# 14_SD.net
KiCad netlist of a schematic drawn in Altium Designer
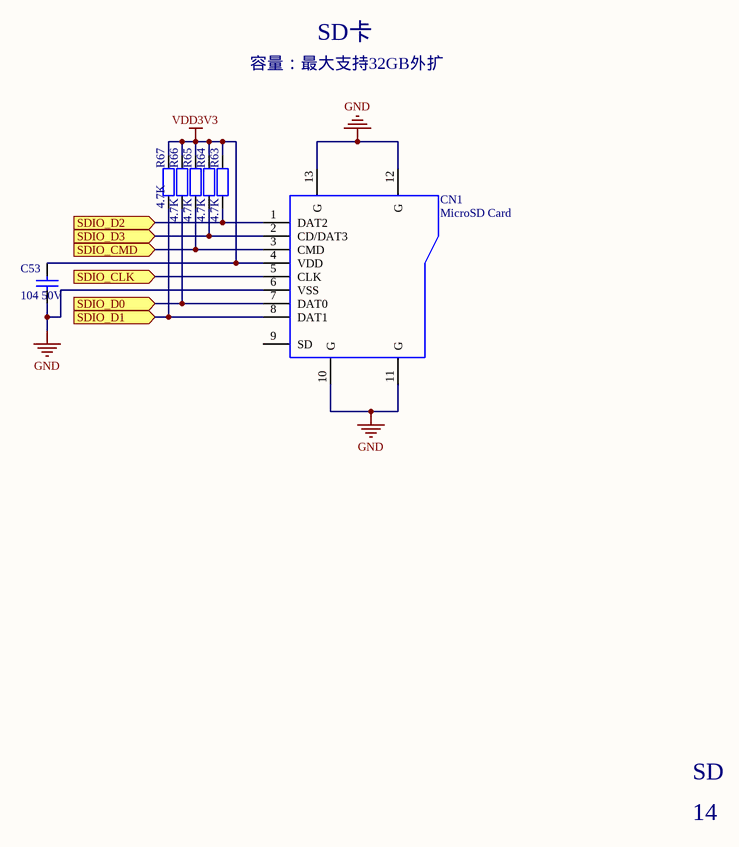
[diagram p0: 14_SD.SchDoc]

(export (version "E")
  (design (tool "Eeschema 10.0.6"))
  (components
    (comp (ref "C53")
      (value "104 50V")
      (footprint "SMD-0603C")
      (description "贴片电容 20%")
      (libsource (lib "XiaoyI") (part "CAP4"))
    )
    (comp (ref "CN1")
      (value "MicroSD Card")
      (footprint "SD_Card_TF")
      (libsource (lib "YS-F1Pro开发板主板") (part "SD Card"))
    )
    (comp (ref "R63")
      (value "4.7K")
      (footprint "SMD-0603")
      (description "贴片电阻 5%")
      (libsource (lib "XiaoyI") (part "RES2"))
    )
    (comp (ref "R64")
      (value "4.7K")
      (footprint "SMD-0603")
      (description "贴片电阻 5%")
      (libsource (lib "XiaoyI") (part "RES2"))
    )
    (comp (ref "R65")
      (value "4.7K")
      (footprint "SMD-0603")
      (description "贴片电阻 5%")
      (libsource (lib "XiaoyI") (part "RES2"))
    )
    (comp (ref "R66")
      (value "4.7K")
      (footprint "SMD-0603")
      (description "贴片电阻 5%")
      (libsource (lib "XiaoyI") (part "RES2"))
    )
    (comp (ref "R67")
      (value "4.7K")
      (footprint "SMD-0603")
      (description "贴片电阻 5%")
      (libsource (lib "XiaoyI") (part "RES2"))
    )
  )
  (nets
    (net (code "1") (name "/SDIO_CLK") (class "Default")
      (node (ref "CN1") (pin "5") (pinfunction "CLK_5") (pintype "passive"))
    )
    (net (code "2") (name "/SDIO_CMD") (class "Default")
      (node (ref "CN1") (pin "3") (pinfunction "CMD_3") (pintype "passive"))
      (node (ref "R65") (pin "2") (pinfunction "2_2") (pintype "passive"))
    )
    (net (code "3") (name "/SDIO_D0") (class "Default")
      (node (ref "CN1") (pin "7") (pinfunction "DAT0_7") (pintype "passive"))
      (node (ref "R66") (pin "2") (pinfunction "2_2") (pintype "passive"))
    )
    (net (code "4") (name "/SDIO_D1") (class "Default")
      (node (ref "CN1") (pin "8") (pinfunction "DAT1_8") (pintype "passive"))
      (node (ref "R67") (pin "2") (pinfunction "2_2") (pintype "passive"))
    )
    (net (code "5") (name "/SDIO_D2") (class "Default")
      (node (ref "CN1") (pin "1") (pinfunction "DAT2_1") (pintype "passive"))
      (node (ref "R63") (pin "2") (pinfunction "2_2") (pintype "passive"))
    )
    (net (code "6") (name "/SDIO_D3") (class "Default")
      (node (ref "CN1") (pin "2") (pinfunction "CD/DAT3_2") (pintype "passive"))
      (node (ref "R64") (pin "2") (pinfunction "2_2") (pintype "passive"))
    )
    (net (code "7") (name "GND") (class "Default")
      (node (ref "C53") (pin "2") (pinfunction "2_2") (pintype "passive"))
      (node (ref "CN1") (pin "10") (pinfunction "G_10") (pintype "passive"))
      (node (ref "CN1") (pin "11") (pinfunction "G_11") (pintype "passive"))
      (node (ref "CN1") (pin "12") (pinfunction "G_12") (pintype "passive"))
      (node (ref "CN1") (pin "13") (pinfunction "G_13") (pintype "passive"))
      (node (ref "CN1") (pin "6") (pinfunction "VSS_6") (pintype "passive"))
    )
    (net (code "8") (name "VDD3V3") (class "Default")
      (node (ref "C53") (pin "1") (pinfunction "1_1") (pintype "passive"))
      (node (ref "CN1") (pin "4") (pinfunction "VDD_4") (pintype "passive"))
      (node (ref "R63") (pin "1") (pinfunction "1_1") (pintype "passive"))
      (node (ref "R64") (pin "1") (pinfunction "1_1") (pintype "passive"))
      (node (ref "R65") (pin "1") (pinfunction "1_1") (pintype "passive"))
      (node (ref "R66") (pin "1") (pinfunction "1_1") (pintype "passive"))
      (node (ref "R67") (pin "1") (pinfunction "1_1") (pintype "passive"))
    )
    (net (code "9") (name "unconnected-(CN1-SD-Pad9)") (class "Default")
      (node (ref "CN1") (pin "9") (pinfunction "SD_9") (pintype "passive"))
    )
  )
)
